# buttons.net
KiCad netlist of a schematic drawn in Altium Designer
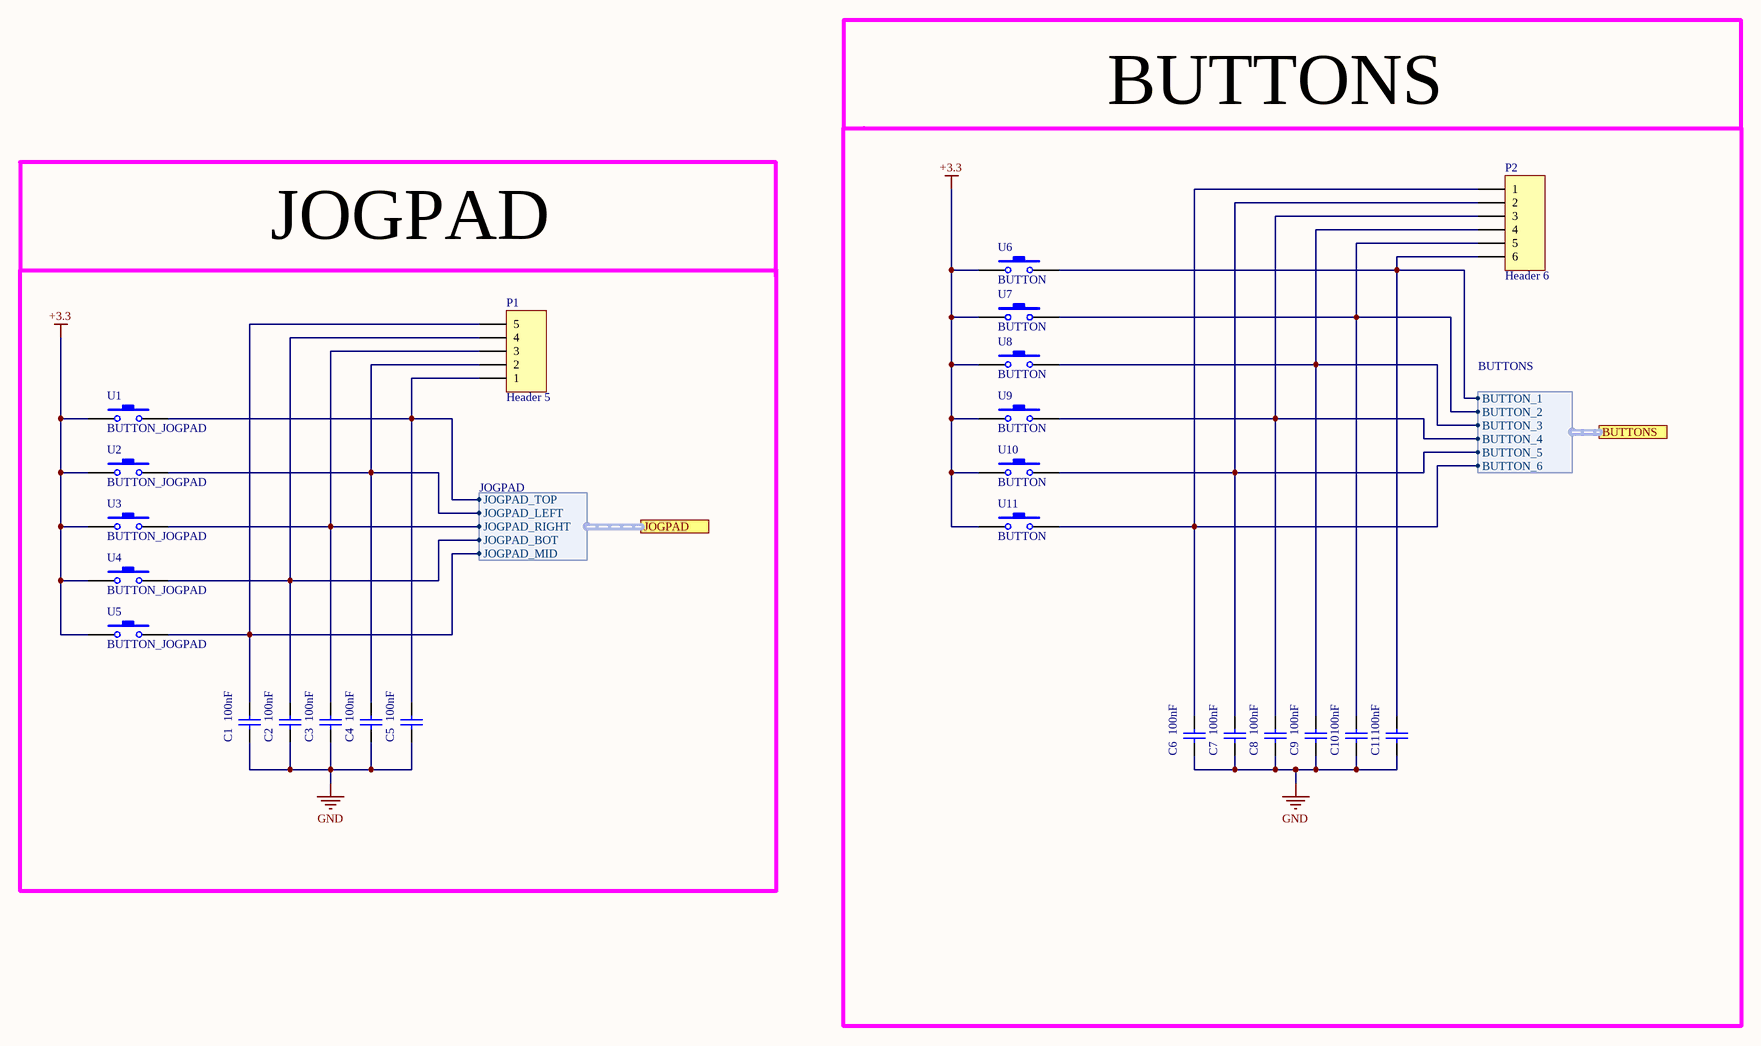
[diagram p0: buttons.SchDoc]

(export (version "E")
  (design (tool "Eeschema 10.0.6"))
  (components
    (comp (ref "C1")
      (value "100nF")
      (footprint "CAP_0402i_1005m -N")
      (description "capacitor")
      (libsource (lib "IDSC std generic parts") (part "Cap"))
    )
    (comp (ref "C2")
      (value "100nF")
      (footprint "CAP_0402i_1005m -N")
      (description "capacitor")
      (libsource (lib "IDSC std generic parts") (part "Cap"))
    )
    (comp (ref "C3")
      (value "100nF")
      (footprint "CAP_0402i_1005m -N")
      (description "capacitor")
      (libsource (lib "IDSC std generic parts") (part "Cap"))
    )
    (comp (ref "C4")
      (value "100nF")
      (footprint "CAP_0402i_1005m -N")
      (description "capacitor")
      (libsource (lib "IDSC std generic parts") (part "Cap"))
    )
    (comp (ref "C5")
      (value "100nF")
      (footprint "CAP_0402i_1005m -N")
      (description "capacitor")
      (libsource (lib "IDSC std generic parts") (part "Cap"))
    )
    (comp (ref "C6")
      (value "100nF")
      (footprint "CAP_0402i_1005m -N")
      (description "capacitor")
      (libsource (lib "IDSC std generic parts") (part "Cap"))
    )
    (comp (ref "C7")
      (value "100nF")
      (footprint "CAP_0402i_1005m -N")
      (description "capacitor")
      (libsource (lib "IDSC std generic parts") (part "Cap"))
    )
    (comp (ref "C8")
      (value "100nF")
      (footprint "CAP_0402i_1005m -N")
      (description "capacitor")
      (libsource (lib "IDSC std generic parts") (part "Cap"))
    )
    (comp (ref "C9")
      (value "100nF")
      (footprint "CAP_0402i_1005m -N")
      (description "capacitor")
      (libsource (lib "IDSC std generic parts") (part "Cap"))
    )
    (comp (ref "C10")
      (value "100nF")
      (footprint "CAP_0402i_1005m -N")
      (description "capacitor")
      (libsource (lib "IDSC std generic parts") (part "Cap"))
    )
    (comp (ref "C11")
      (value "100nF")
      (footprint "CAP_0402i_1005m -N")
      (description "capacitor")
      (libsource (lib "IDSC std generic parts") (part "Cap"))
    )
    (comp (ref "P1")
      (value "Header 5")
      (footprint "HDR1X5")
      (description "Header, 5-Pin")
      (libsource (lib "IDSC std connectors") (part "Header 5"))
    )
    (comp (ref "P2")
      (value "Header 6")
      (footprint "HDR1X6")
      (description "Header, 6-Pin")
      (libsource (lib "IDSC std connectors") (part "Header 6"))
    )
    (comp (ref "U1")
      (value "BUTTON_JOGPAD")
      (footprint "JOGPAD_Button")
      (libsource (lib "BMA_lib") (part "BUTTON_JOGPAD"))
    )
    (comp (ref "U2")
      (value "BUTTON_JOGPAD")
      (footprint "JOGPAD_Button")
      (libsource (lib "BMA_lib") (part "BUTTON_JOGPAD"))
    )
    (comp (ref "U3")
      (value "BUTTON_JOGPAD")
      (footprint "JOGPAD_Button")
      (libsource (lib "BMA_lib") (part "BUTTON_JOGPAD"))
    )
    (comp (ref "U4")
      (value "BUTTON_JOGPAD")
      (footprint "JOGPAD_Button")
      (libsource (lib "BMA_lib") (part "BUTTON_JOGPAD"))
    )
    (comp (ref "U5")
      (value "BUTTON_JOGPAD")
      (footprint "JOGPAD_Button")
      (libsource (lib "BMA_lib") (part "BUTTON_JOGPAD"))
    )
    (comp (ref "U6") (value "BUTTON") (footprint "RND 210-00206") (libsource (lib "BMA_lib") (part "BUTTON")))
    (comp (ref "U7") (value "BUTTON") (footprint "RND 210-00206") (libsource (lib "BMA_lib") (part "BUTTON")))
    (comp (ref "U8") (value "BUTTON") (footprint "RND 210-00206") (libsource (lib "BMA_lib") (part "BUTTON")))
    (comp (ref "U9") (value "BUTTON") (footprint "RND 210-00206") (libsource (lib "BMA_lib") (part "BUTTON")))
    (comp (ref "U10")
      (value "BUTTON")
      (footprint "RND 210-00206")
      (libsource (lib "BMA_lib") (part "BUTTON"))
    )
    (comp (ref "U11")
      (value "BUTTON")
      (footprint "RND 210-00206")
      (libsource (lib "BMA_lib") (part "BUTTON"))
    )
  )
  (nets
    (net (code "3") (name "+3.3") (class "Default")
      (node (ref "U1") (pin "1") (pinfunction "1_1") (pintype "passive"))
      (node (ref "U10") (pin "1") (pinfunction "1_1") (pintype "passive"))
      (node (ref "U11") (pin "1") (pinfunction "1_1") (pintype "passive"))
      (node (ref "U2") (pin "1") (pinfunction "1_1") (pintype "passive"))
      (node (ref "U3") (pin "1") (pinfunction "1_1") (pintype "passive"))
      (node (ref "U4") (pin "1") (pinfunction "1_1") (pintype "passive"))
      (node (ref "U5") (pin "1") (pinfunction "1_1") (pintype "passive"))
      (node (ref "U6") (pin "1") (pinfunction "1_1") (pintype "passive"))
      (node (ref "U7") (pin "1") (pinfunction "1_1") (pintype "passive"))
      (node (ref "U8") (pin "1") (pinfunction "1_1") (pintype "passive"))
      (node (ref "U9") (pin "1") (pinfunction "1_1") (pintype "passive"))
    )
    (net (code "6") (name "GND") (class "Default")
      (node (ref "C1") (pin "1") (pinfunction "1_1") (pintype "passive"))
      (node (ref "C10") (pin "1") (pinfunction "1_1") (pintype "passive"))
      (node (ref "C11") (pin "1") (pinfunction "1_1") (pintype "passive"))
      (node (ref "C2") (pin "1") (pinfunction "1_1") (pintype "passive"))
      (node (ref "C3") (pin "1") (pinfunction "1_1") (pintype "passive"))
      (node (ref "C4") (pin "1") (pinfunction "1_1") (pintype "passive"))
      (node (ref "C5") (pin "1") (pinfunction "1_1") (pintype "passive"))
      (node (ref "C6") (pin "1") (pinfunction "1_1") (pintype "passive"))
      (node (ref "C7") (pin "1") (pinfunction "1_1") (pintype "passive"))
      (node (ref "C8") (pin "1") (pinfunction "1_1") (pintype "passive"))
      (node (ref "C9") (pin "1") (pinfunction "1_1") (pintype "passive"))
    )
    (net (code "7") (name "Net-(C1-Pad2)") (class "Default")
      (node (ref "C1") (pin "2") (pinfunction "2_2") (pintype "passive"))
      (node (ref "P1") (pin "5") (pinfunction "5_5") (pintype "passive"))
      (node (ref "U5") (pin "2") (pinfunction "2_2") (pintype "passive"))
    )
    (net (code "8") (name "Net-(C2-Pad2)") (class "Default")
      (node (ref "C2") (pin "2") (pinfunction "2_2") (pintype "passive"))
      (node (ref "P1") (pin "4") (pinfunction "4_4") (pintype "passive"))
      (node (ref "U4") (pin "2") (pinfunction "2_2") (pintype "passive"))
    )
    (net (code "9") (name "Net-(C3-Pad2)") (class "Default")
      (node (ref "C3") (pin "2") (pinfunction "2_2") (pintype "passive"))
      (node (ref "P1") (pin "3") (pinfunction "3_3") (pintype "passive"))
      (node (ref "U3") (pin "2") (pinfunction "2_2") (pintype "passive"))
    )
    (net (code "10") (name "Net-(C4-Pad2)") (class "Default")
      (node (ref "C4") (pin "2") (pinfunction "2_2") (pintype "passive"))
      (node (ref "P1") (pin "2") (pinfunction "2_2") (pintype "passive"))
      (node (ref "U2") (pin "2") (pinfunction "2_2") (pintype "passive"))
    )
    (net (code "11") (name "Net-(C5-Pad2)") (class "Default")
      (node (ref "C5") (pin "2") (pinfunction "2_2") (pintype "passive"))
      (node (ref "P1") (pin "1") (pinfunction "1_1") (pintype "passive"))
      (node (ref "U1") (pin "2") (pinfunction "2_2") (pintype "passive"))
    )
    (net (code "12") (name "Net-(C6-Pad2)") (class "Default")
      (node (ref "C6") (pin "2") (pinfunction "2_2") (pintype "passive"))
      (node (ref "P2") (pin "1") (pinfunction "1_1") (pintype "passive"))
      (node (ref "U11") (pin "2") (pinfunction "2_2") (pintype "passive"))
    )
    (net (code "13") (name "Net-(C7-Pad2)") (class "Default")
      (node (ref "C7") (pin "2") (pinfunction "2_2") (pintype "passive"))
      (node (ref "P2") (pin "2") (pinfunction "2_2") (pintype "passive"))
      (node (ref "U10") (pin "2") (pinfunction "2_2") (pintype "passive"))
    )
    (net (code "14") (name "Net-(C8-Pad2)") (class "Default")
      (node (ref "C8") (pin "2") (pinfunction "2_2") (pintype "passive"))
      (node (ref "P2") (pin "3") (pinfunction "3_3") (pintype "passive"))
      (node (ref "U9") (pin "2") (pinfunction "2_2") (pintype "passive"))
    )
    (net (code "15") (name "Net-(C9-Pad2)") (class "Default")
      (node (ref "C9") (pin "2") (pinfunction "2_2") (pintype "passive"))
      (node (ref "P2") (pin "4") (pinfunction "4_4") (pintype "passive"))
      (node (ref "U8") (pin "2") (pinfunction "2_2") (pintype "passive"))
    )
    (net (code "16") (name "Net-(C10-Pad2)") (class "Default")
      (node (ref "C10") (pin "2") (pinfunction "2_2") (pintype "passive"))
      (node (ref "P2") (pin "5") (pinfunction "5_5") (pintype "passive"))
      (node (ref "U7") (pin "2") (pinfunction "2_2") (pintype "passive"))
    )
    (net (code "17") (name "Net-(C11-Pad2)") (class "Default")
      (node (ref "C11") (pin "2") (pinfunction "2_2") (pintype "passive"))
      (node (ref "P2") (pin "6") (pinfunction "6_6") (pintype "passive"))
      (node (ref "U6") (pin "2") (pinfunction "2_2") (pintype "passive"))
    )
  )
)
